# latch_circuit.net
KiCad netlist of a schematic drawn in EAGLE
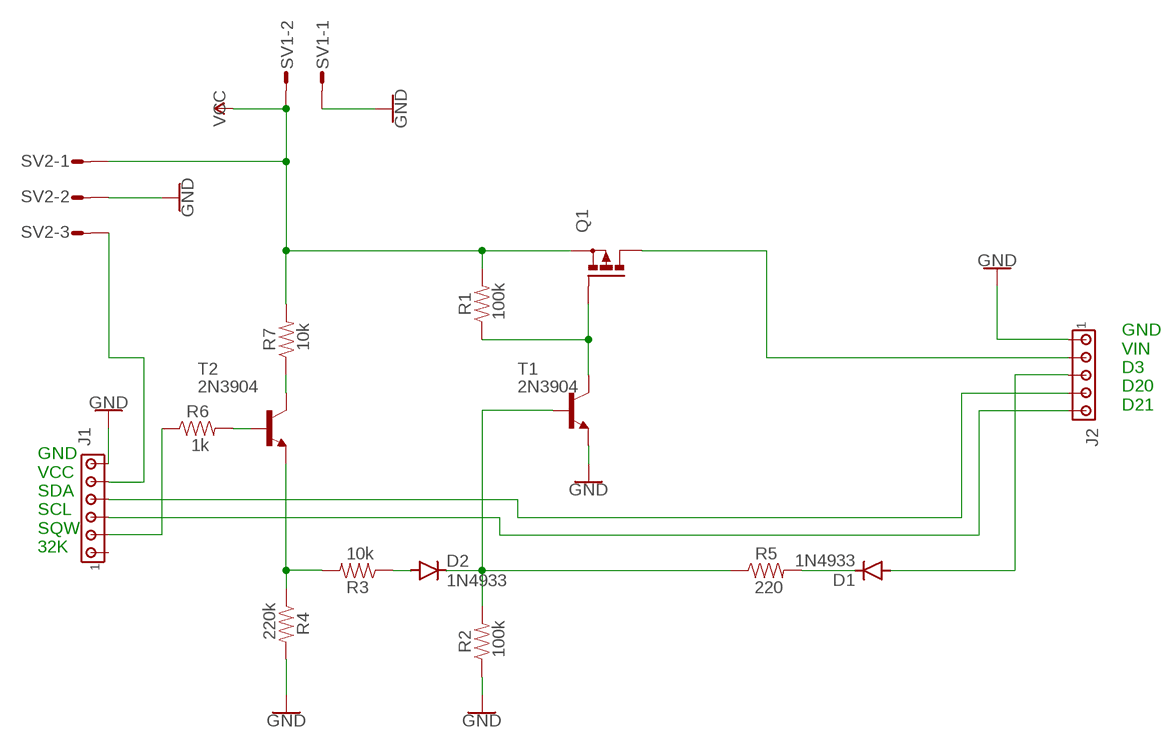
[diagram p0: schematic, sheet 1]

(export (version "E")
  (design (tool "Eeschema 10.0.6"))
  (components
    (comp (ref "D1")
      (value "1N4933")
      (footprint "eagle-import:DO41-10")
      (libsource (lib "eagle-import") (part "1N4933"))
    )
    (comp (ref "D2")
      (value "1N4933")
      (footprint "eagle-import:DO41-10")
      (libsource (lib "eagle-import") (part "1N4933"))
    )
    (comp (ref "J1")
      (value "MTA06-100")
      (footprint "eagle-import:10X06MTA")
      (libsource (lib "eagle-import") (part "MTA06-100"))
    )
    (comp (ref "J2")
      (value "MTA05-100")
      (footprint "eagle-import:10X05MTA")
      (libsource (lib "eagle-import") (part "MTA05-100"))
    )
    (comp (ref "Q1")
      (value "PMOSFET_PTO220BH")
      (footprint "eagle-import:TO220BH")
      (libsource (lib "eagle-import") (part "PMOSFET_PTO220BH"))
    )
    (comp (ref "R1")
      (value "100k")
      (footprint "eagle-import:AXIAL-0.3")
      (libsource (lib "eagle-import") (part "RESISTORAXIAL-0.3"))
    )
    (comp (ref "R2")
      (value "100k")
      (footprint "eagle-import:AXIAL-0.3")
      (libsource (lib "eagle-import") (part "RESISTORAXIAL-0.3"))
    )
    (comp (ref "R3")
      (value "10k")
      (footprint "eagle-import:AXIAL-0.3")
      (libsource (lib "eagle-import") (part "RESISTORAXIAL-0.3"))
    )
    (comp (ref "R4")
      (value "220k")
      (footprint "eagle-import:AXIAL-0.3")
      (libsource (lib "eagle-import") (part "RESISTORAXIAL-0.3"))
    )
    (comp (ref "R5")
      (value "220")
      (footprint "eagle-import:AXIAL-0.3")
      (libsource (lib "eagle-import") (part "RESISTORAXIAL-0.3"))
    )
    (comp (ref "R6")
      (value "1k")
      (footprint "eagle-import:AXIAL-0.3")
      (libsource (lib "eagle-import") (part "RESISTORAXIAL-0.3"))
    )
    (comp (ref "R7")
      (value "10k")
      (footprint "eagle-import:AXIAL-0.3")
      (libsource (lib "eagle-import") (part "RESISTORAXIAL-0.3"))
    )
    (comp (ref "SV1")
      (value "S02P")
      (footprint "eagle-import:S02P")
      (libsource (lib "eagle-import") (part "S02P"))
    )
    (comp (ref "SV2")
      (value "S03P")
      (footprint "eagle-import:S03P")
      (libsource (lib "eagle-import") (part "S03P"))
    )
    (comp (ref "T1")
      (value "2N3904")
      (footprint "eagle-import:TO92")
      (libsource (lib "eagle-import") (part "2N3904"))
    )
    (comp (ref "T2")
      (value "2N3904")
      (footprint "eagle-import:TO92")
      (libsource (lib "eagle-import") (part "2N3904"))
    )
  )
  (nets
    (net (code "1") (name "GND") (class "Default")
      (node (ref "J1") (pin "6") (pinfunction "6_6") (pintype "passive"))
      (node (ref "J2") (pin "1") (pinfunction "1_1") (pintype "passive"))
      (node (ref "R2") (pin "P$1") (pinfunction "1_P$1") (pintype "passive"))
      (node (ref "R4") (pin "P$2") (pinfunction "2_P$2") (pintype "passive"))
      (node (ref "SV1") (pin "1") (pinfunction "S_1") (pintype "passive"))
      (node (ref "SV2") (pin "2") (pinfunction "S_2") (pintype "passive"))
      (node (ref "T1") (pin "3") (pinfunction "E_3") (pintype "passive"))
    )
    (net (code "2") (name "Net-(D1-PadA)") (class "Default")
      (node (ref "D1") (pin "A") (pinfunction "A_A") (pintype "passive"))
      (node (ref "J2") (pin "3") (pinfunction "3_3") (pintype "passive"))
    )
    (net (code "3") (name "Net-(J1-Pad3)") (class "Default")
      (node (ref "J1") (pin "3") (pinfunction "3_3") (pintype "passive"))
      (node (ref "J2") (pin "5") (pinfunction "5_5") (pintype "passive"))
    )
    (net (code "4") (name "Net-(J1-Pad4)") (class "Default")
      (node (ref "J1") (pin "4") (pinfunction "4_4") (pintype "passive"))
      (node (ref "J2") (pin "4") (pinfunction "4_4") (pintype "passive"))
    )
    (net (code "5") (name "Net-(J2-Pad2)") (class "Default")
      (node (ref "J2") (pin "2") (pinfunction "2_2") (pintype "passive"))
      (node (ref "Q1") (pin "D") (pinfunction "D_D") (pintype "passive"))
    )
    (net (code "6") (name "Net-(R1-1)") (class "Default")
      (node (ref "Q1") (pin "G") (pinfunction "G_G") (pintype "passive"))
      (node (ref "R1") (pin "P$1") (pinfunction "1_P$1") (pintype "passive"))
      (node (ref "T1") (pin "1") (pinfunction "C_1") (pintype "passive"))
    )
    (net (code "7") (name "Net-(R2-2)") (class "Default")
      (node (ref "D2") (pin "C") (pinfunction "C_C") (pintype "passive"))
      (node (ref "R2") (pin "P$2") (pinfunction "2_P$2") (pintype "passive"))
      (node (ref "R5") (pin "P$1") (pinfunction "1_P$1") (pintype "passive"))
      (node (ref "T1") (pin "2") (pinfunction "B_2") (pintype "passive"))
    )
    (net (code "8") (name "Net-(R3-1)") (class "Default")
      (node (ref "D2") (pin "A") (pinfunction "A_A") (pintype "passive"))
      (node (ref "R3") (pin "P$1") (pinfunction "1_P$1") (pintype "passive"))
    )
    (net (code "9") (name "Net-(R3-2)") (class "Default")
      (node (ref "R3") (pin "P$2") (pinfunction "2_P$2") (pintype "passive"))
      (node (ref "R4") (pin "P$1") (pinfunction "1_P$1") (pintype "passive"))
      (node (ref "T2") (pin "3") (pinfunction "E_3") (pintype "passive"))
    )
    (net (code "10") (name "Net-(R5-2)") (class "Default")
      (node (ref "D1") (pin "C") (pinfunction "C_C") (pintype "passive"))
      (node (ref "R5") (pin "P$2") (pinfunction "2_P$2") (pintype "passive"))
    )
    (net (code "11") (name "Net-(R6-1)") (class "Default")
      (node (ref "J1") (pin "2") (pinfunction "2_2") (pintype "passive"))
      (node (ref "R6") (pin "P$1") (pinfunction "1_P$1") (pintype "passive"))
    )
    (net (code "12") (name "Net-(R6-2)") (class "Default")
      (node (ref "R6") (pin "P$2") (pinfunction "2_P$2") (pintype "passive"))
      (node (ref "T2") (pin "2") (pinfunction "B_2") (pintype "passive"))
    )
    (net (code "13") (name "Net-(R7-1)") (class "Default")
      (node (ref "R7") (pin "P$1") (pinfunction "1_P$1") (pintype "passive"))
      (node (ref "T2") (pin "1") (pinfunction "C_1") (pintype "passive"))
    )
    (net (code "14") (name "Net-(SV2C-S)") (class "Default")
      (node (ref "J1") (pin "5") (pinfunction "5_5") (pintype "passive"))
      (node (ref "SV2") (pin "3") (pinfunction "S_3") (pintype "passive"))
    )
    (net (code "15") (name "VCC") (class "Default")
      (node (ref "Q1") (pin "S") (pinfunction "S_S") (pintype "passive"))
      (node (ref "R1") (pin "P$2") (pinfunction "2_P$2") (pintype "passive"))
      (node (ref "R7") (pin "P$2") (pinfunction "2_P$2") (pintype "passive"))
      (node (ref "SV1") (pin "2") (pinfunction "S_2") (pintype "passive"))
      (node (ref "SV2") (pin "1") (pinfunction "S_1") (pintype "passive"))
    )
    (net (code "16") (name "unconnected-(J1-Pad1)") (class "Default")
      (node (ref "J1") (pin "1") (pinfunction "1_1") (pintype "passive"))
    )
  )
)
